# cpu2_lock_control2.net
KiCad netlist of a schematic drawn in Altium Designer
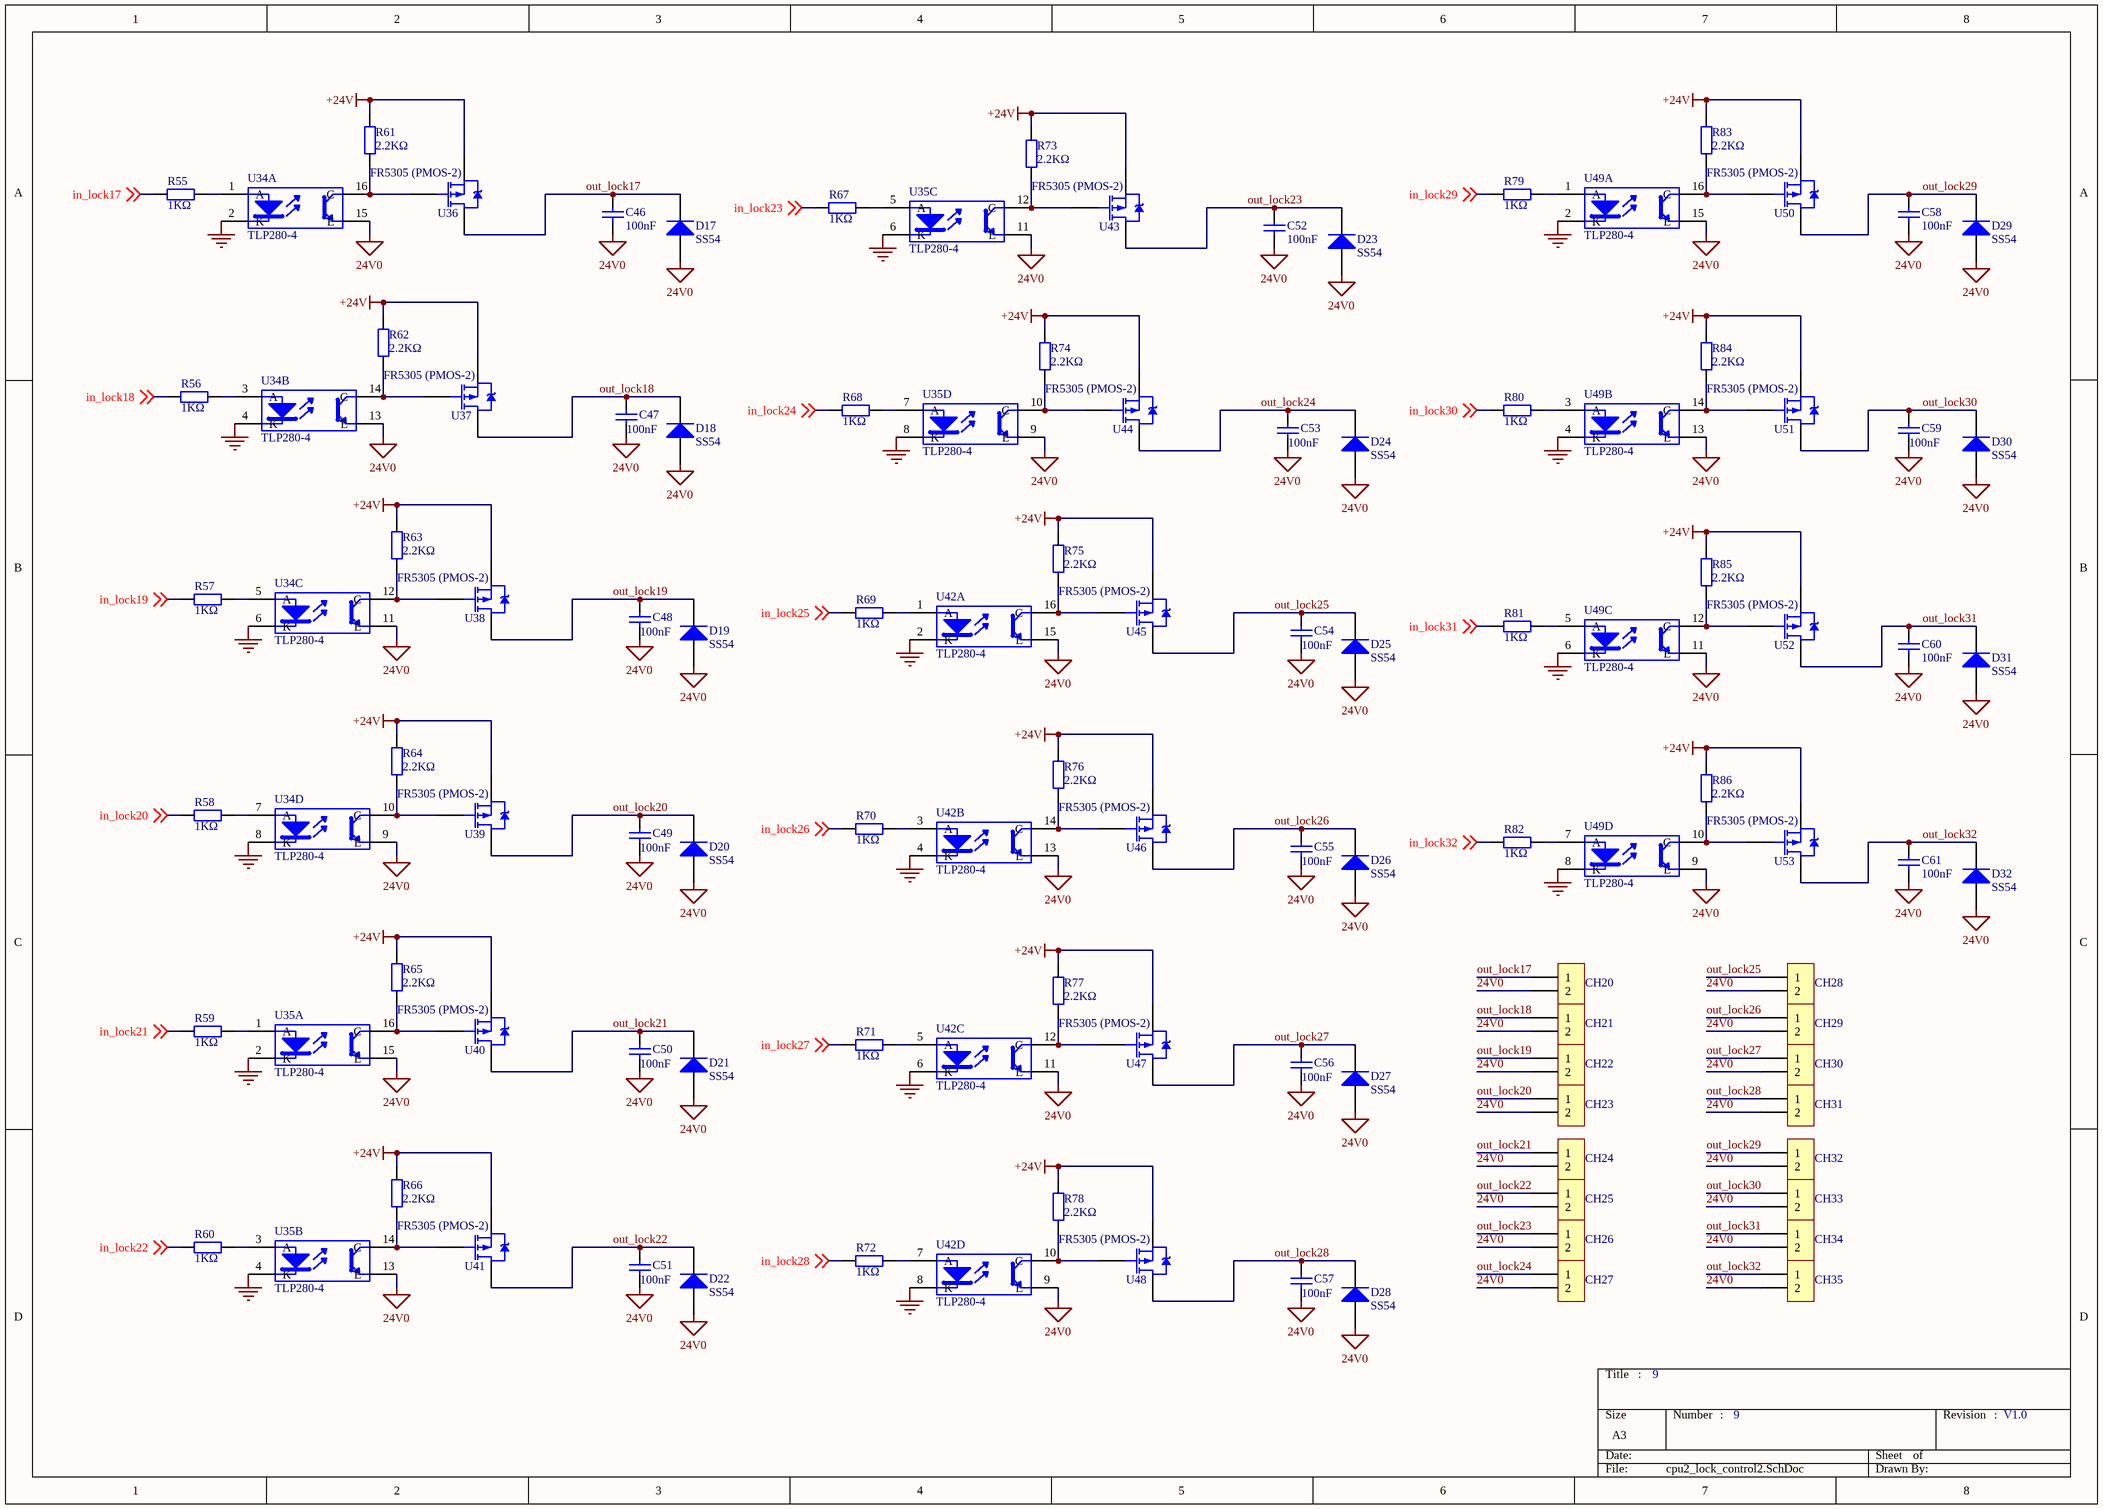
[diagram p0: cpu2_lock_control2.SchDoc]

(export (version "E")
  (design (tool "Eeschema 10.0.6"))
  (components
    (comp (ref "C46")
      (value "100nF")
      (footprint "0805_C")
      (description "贴片电容")
      (libsource (lib "Miscellaneous Devices LC") (part "0805 100nF(104) 10% 50V"))
    )
    (comp (ref "C47")
      (value "100nF")
      (footprint "0805_C")
      (description "贴片电容")
      (libsource (lib "Miscellaneous Devices LC") (part "0805 100nF(104) 10% 50V"))
    )
    (comp (ref "C48")
      (value "100nF")
      (footprint "0805_C")
      (description "贴片电容")
      (libsource (lib "Miscellaneous Devices LC") (part "0805 100nF(104) 10% 50V"))
    )
    (comp (ref "C49")
      (value "100nF")
      (footprint "0805_C")
      (description "贴片电容")
      (libsource (lib "Miscellaneous Devices LC") (part "0805 100nF(104) 10% 50V"))
    )
    (comp (ref "C50")
      (value "100nF")
      (footprint "0805_C")
      (description "贴片电容")
      (libsource (lib "Miscellaneous Devices LC") (part "0805 100nF(104) 10% 50V"))
    )
    (comp (ref "C51")
      (value "100nF")
      (footprint "0805_C")
      (description "贴片电容")
      (libsource (lib "Miscellaneous Devices LC") (part "0805 100nF(104) 10% 50V"))
    )
    (comp (ref "C52")
      (value "100nF")
      (footprint "0805_C")
      (description "贴片电容")
      (libsource (lib "Miscellaneous Devices LC") (part "0805 100nF(104) 10% 50V"))
    )
    (comp (ref "C53")
      (value "100nF")
      (footprint "0805_C")
      (description "贴片电容")
      (libsource (lib "Miscellaneous Devices LC") (part "0805 100nF(104) 10% 50V"))
    )
    (comp (ref "C54")
      (value "100nF")
      (footprint "0805_C")
      (description "贴片电容")
      (libsource (lib "Miscellaneous Devices LC") (part "0805 100nF(104) 10% 50V"))
    )
    (comp (ref "C55")
      (value "100nF")
      (footprint "0805_C")
      (description "贴片电容")
      (libsource (lib "Miscellaneous Devices LC") (part "0805 100nF(104) 10% 50V"))
    )
    (comp (ref "C56")
      (value "100nF")
      (footprint "0805_C")
      (description "贴片电容")
      (libsource (lib "Miscellaneous Devices LC") (part "0805 100nF(104) 10% 50V"))
    )
    (comp (ref "C57")
      (value "100nF")
      (footprint "0805_C")
      (description "贴片电容")
      (libsource (lib "Miscellaneous Devices LC") (part "0805 100nF(104) 10% 50V"))
    )
    (comp (ref "C58")
      (value "100nF")
      (footprint "0805_C")
      (description "贴片电容")
      (libsource (lib "Miscellaneous Devices LC") (part "0805 100nF(104) 10% 50V"))
    )
    (comp (ref "C59")
      (value "100nF")
      (footprint "0805_C")
      (description "贴片电容")
      (libsource (lib "Miscellaneous Devices LC") (part "0805 100nF(104) 10% 50V"))
    )
    (comp (ref "C60")
      (value "100nF")
      (footprint "0805_C")
      (description "贴片电容")
      (libsource (lib "Miscellaneous Devices LC") (part "0805 100nF(104) 10% 50V"))
    )
    (comp (ref "C61")
      (value "100nF")
      (footprint "0805_C")
      (description "贴片电容")
      (libsource (lib "Miscellaneous Devices LC") (part "0805 100nF(104) 10% 50V"))
    )
    (comp (ref "CH20")
      (value "HEADER1X2")
      (footprint "CH3.96-2PIN")
      (libsource (lib "myIntegrated_Library1") (part "HEADER1X2"))
    )
    (comp (ref "CH21")
      (value "HEADER1X2")
      (footprint "CH3.96-2PIN")
      (libsource (lib "myIntegrated_Library1") (part "HEADER1X2"))
    )
    (comp (ref "CH22")
      (value "HEADER1X2")
      (footprint "CH3.96-2PIN")
      (libsource (lib "myIntegrated_Library1") (part "HEADER1X2"))
    )
    (comp (ref "CH23")
      (value "HEADER1X2")
      (footprint "CH3.96-2PIN")
      (libsource (lib "myIntegrated_Library1") (part "HEADER1X2"))
    )
    (comp (ref "CH24")
      (value "HEADER1X2")
      (footprint "CH3.96-2PIN")
      (libsource (lib "myIntegrated_Library1") (part "HEADER1X2"))
    )
    (comp (ref "CH25")
      (value "HEADER1X2")
      (footprint "CH3.96-2PIN")
      (libsource (lib "myIntegrated_Library1") (part "HEADER1X2"))
    )
    (comp (ref "CH26")
      (value "HEADER1X2")
      (footprint "CH3.96-2PIN")
      (libsource (lib "myIntegrated_Library1") (part "HEADER1X2"))
    )
    (comp (ref "CH27")
      (value "HEADER1X2")
      (footprint "CH3.96-2PIN")
      (libsource (lib "myIntegrated_Library1") (part "HEADER1X2"))
    )
    (comp (ref "CH28")
      (value "HEADER1X2")
      (footprint "CH3.96-2PIN")
      (libsource (lib "myIntegrated_Library1") (part "HEADER1X2"))
    )
    (comp (ref "CH29")
      (value "HEADER1X2")
      (footprint "CH3.96-2PIN")
      (libsource (lib "myIntegrated_Library1") (part "HEADER1X2"))
    )
    (comp (ref "CH30")
      (value "HEADER1X2")
      (footprint "CH3.96-2PIN")
      (libsource (lib "myIntegrated_Library1") (part "HEADER1X2"))
    )
    (comp (ref "CH31")
      (value "HEADER1X2")
      (footprint "CH3.96-2PIN")
      (libsource (lib "myIntegrated_Library1") (part "HEADER1X2"))
    )
    (comp (ref "CH32")
      (value "HEADER1X2")
      (footprint "CH3.96-2PIN")
      (libsource (lib "myIntegrated_Library1") (part "HEADER1X2"))
    )
    (comp (ref "CH33")
      (value "HEADER1X2")
      (footprint "CH3.96-2PIN")
      (libsource (lib "myIntegrated_Library1") (part "HEADER1X2"))
    )
    (comp (ref "CH34")
      (value "HEADER1X2")
      (footprint "CH3.96-2PIN")
      (libsource (lib "myIntegrated_Library1") (part "HEADER1X2"))
    )
    (comp (ref "CH35")
      (value "HEADER1X2")
      (footprint "CH3.96-2PIN")
      (libsource (lib "myIntegrated_Library1") (part "HEADER1X2"))
    )
    (comp (ref "D17")
      (value "SS54")
      (footprint "SMA(DO-214AC)_S1")
      (description "二极管")
      (libsource (lib "Miscellaneous Devices LC") (part "SMA(DO-214AC) SS54"))
    )
    (comp (ref "D18")
      (value "SS54")
      (footprint "SMA(DO-214AC)_S1")
      (description "二极管")
      (libsource (lib "Miscellaneous Devices LC") (part "SMA(DO-214AC) SS54"))
    )
    (comp (ref "D19")
      (value "SS54")
      (footprint "SMA(DO-214AC)_S1")
      (description "二极管")
      (libsource (lib "Miscellaneous Devices LC") (part "SMA(DO-214AC) SS54"))
    )
    (comp (ref "D20")
      (value "SS54")
      (footprint "SMA(DO-214AC)_S1")
      (description "二极管")
      (libsource (lib "Miscellaneous Devices LC") (part "SMA(DO-214AC) SS54"))
    )
    (comp (ref "D21")
      (value "SS54")
      (footprint "SMA(DO-214AC)_S1")
      (description "二极管")
      (libsource (lib "Miscellaneous Devices LC") (part "SMA(DO-214AC) SS54"))
    )
    (comp (ref "D22")
      (value "SS54")
      (footprint "SMA(DO-214AC)_S1")
      (description "二极管")
      (libsource (lib "Miscellaneous Devices LC") (part "SMA(DO-214AC) SS54"))
    )
    (comp (ref "D23")
      (value "SS54")
      (footprint "SMA(DO-214AC)_S1")
      (description "二极管")
      (libsource (lib "Miscellaneous Devices LC") (part "SMA(DO-214AC) SS54"))
    )
    (comp (ref "D24")
      (value "SS54")
      (footprint "SMA(DO-214AC)_S1")
      (description "二极管")
      (libsource (lib "Miscellaneous Devices LC") (part "SMA(DO-214AC) SS54"))
    )
    (comp (ref "D25")
      (value "SS54")
      (footprint "SMA(DO-214AC)_S1")
      (description "二极管")
      (libsource (lib "Miscellaneous Devices LC") (part "SMA(DO-214AC) SS54"))
    )
    (comp (ref "D26")
      (value "SS54")
      (footprint "SMA(DO-214AC)_S1")
      (description "二极管")
      (libsource (lib "Miscellaneous Devices LC") (part "SMA(DO-214AC) SS54"))
    )
    (comp (ref "D27")
      (value "SS54")
      (footprint "SMA(DO-214AC)_S1")
      (description "二极管")
      (libsource (lib "Miscellaneous Devices LC") (part "SMA(DO-214AC) SS54"))
    )
    (comp (ref "D28")
      (value "SS54")
      (footprint "SMA(DO-214AC)_S1")
      (description "二极管")
      (libsource (lib "Miscellaneous Devices LC") (part "SMA(DO-214AC) SS54"))
    )
    (comp (ref "D29")
      (value "SS54")
      (footprint "SMA(DO-214AC)_S1")
      (description "二极管")
      (libsource (lib "Miscellaneous Devices LC") (part "SMA(DO-214AC) SS54"))
    )
    (comp (ref "D30")
      (value "SS54")
      (footprint "SMA(DO-214AC)_S1")
      (description "二极管")
      (libsource (lib "Miscellaneous Devices LC") (part "SMA(DO-214AC) SS54"))
    )
    (comp (ref "D31")
      (value "SS54")
      (footprint "SMA(DO-214AC)_S1")
      (description "二极管")
      (libsource (lib "Miscellaneous Devices LC") (part "SMA(DO-214AC) SS54"))
    )
    (comp (ref "D32")
      (value "SS54")
      (footprint "SMA(DO-214AC)_S1")
      (description "二极管")
      (libsource (lib "Miscellaneous Devices LC") (part "SMA(DO-214AC) SS54"))
    )
    (comp (ref "R55")
      (value "1KΩ")
      (footprint "0805_R")
      (description "贴片电阻")
      (libsource (lib "") (part "0805 11KΩ (1102) 1%_1"))
    )
    (comp (ref "R56")
      (value "1KΩ")
      (footprint "0805_R")
      (description "贴片电阻")
      (libsource (lib "") (part "0805 11KΩ (1102) 1%_1"))
    )
    (comp (ref "R57")
      (value "1KΩ")
      (footprint "0805_R")
      (description "贴片电阻")
      (libsource (lib "") (part "0805 11KΩ (1102) 1%_1"))
    )
    (comp (ref "R58")
      (value "1KΩ")
      (footprint "0805_R")
      (description "贴片电阻")
      (libsource (lib "") (part "0805 11KΩ (1102) 1%_1"))
    )
    (comp (ref "R59")
      (value "1KΩ")
      (footprint "0805_R")
      (description "贴片电阻")
      (libsource (lib "") (part "0805 11KΩ (1102) 1%_1"))
    )
    (comp (ref "R60")
      (value "1KΩ")
      (footprint "0805_R")
      (description "贴片电阻")
      (libsource (lib "") (part "0805 11KΩ (1102) 1%_1"))
    )
    (comp (ref "R61")
      (value "2.2KΩ")
      (footprint "0805_R")
      (description "贴片电阻")
      (libsource (lib "Miscellaneous Devices LC") (part "0805 11KΩ (1102) 1%"))
    )
    (comp (ref "R62")
      (value "2.2KΩ")
      (footprint "0805_R")
      (description "贴片电阻")
      (libsource (lib "Miscellaneous Devices LC") (part "0805 11KΩ (1102) 1%"))
    )
    (comp (ref "R63")
      (value "2.2KΩ")
      (footprint "0805_R")
      (description "贴片电阻")
      (libsource (lib "Miscellaneous Devices LC") (part "0805 11KΩ (1102) 1%"))
    )
    (comp (ref "R64")
      (value "2.2KΩ")
      (footprint "0805_R")
      (description "贴片电阻")
      (libsource (lib "Miscellaneous Devices LC") (part "0805 11KΩ (1102) 1%"))
    )
    (comp (ref "R65")
      (value "2.2KΩ")
      (footprint "0805_R")
      (description "贴片电阻")
      (libsource (lib "Miscellaneous Devices LC") (part "0805 11KΩ (1102) 1%"))
    )
    (comp (ref "R66")
      (value "2.2KΩ")
      (footprint "0805_R")
      (description "贴片电阻")
      (libsource (lib "Miscellaneous Devices LC") (part "0805 11KΩ (1102) 1%"))
    )
    (comp (ref "R67")
      (value "1KΩ")
      (footprint "0805_R")
      (description "贴片电阻")
      (libsource (lib "") (part "0805 11KΩ (1102) 1%_1"))
    )
    (comp (ref "R68")
      (value "1KΩ")
      (footprint "0805_R")
      (description "贴片电阻")
      (libsource (lib "") (part "0805 11KΩ (1102) 1%_1"))
    )
    (comp (ref "R69")
      (value "1KΩ")
      (footprint "0805_R")
      (description "贴片电阻")
      (libsource (lib "") (part "0805 11KΩ (1102) 1%_1"))
    )
    (comp (ref "R70")
      (value "1KΩ")
      (footprint "0805_R")
      (description "贴片电阻")
      (libsource (lib "") (part "0805 11KΩ (1102) 1%_1"))
    )
    (comp (ref "R71")
      (value "1KΩ")
      (footprint "0805_R")
      (description "贴片电阻")
      (libsource (lib "") (part "0805 11KΩ (1102) 1%_1"))
    )
    (comp (ref "R72")
      (value "1KΩ")
      (footprint "0805_R")
      (description "贴片电阻")
      (libsource (lib "") (part "0805 11KΩ (1102) 1%_1"))
    )
    (comp (ref "R73")
      (value "2.2KΩ")
      (footprint "0805_R")
      (description "贴片电阻")
      (libsource (lib "Miscellaneous Devices LC") (part "0805 11KΩ (1102) 1%"))
    )
    (comp (ref "R74")
      (value "2.2KΩ")
      (footprint "0805_R")
      (description "贴片电阻")
      (libsource (lib "Miscellaneous Devices LC") (part "0805 11KΩ (1102) 1%"))
    )
    (comp (ref "R75")
      (value "2.2KΩ")
      (footprint "0805_R")
      (description "贴片电阻")
      (libsource (lib "Miscellaneous Devices LC") (part "0805 11KΩ (1102) 1%"))
    )
    (comp (ref "R76")
      (value "2.2KΩ")
      (footprint "0805_R")
      (description "贴片电阻")
      (libsource (lib "Miscellaneous Devices LC") (part "0805 11KΩ (1102) 1%"))
    )
    (comp (ref "R77")
      (value "2.2KΩ")
      (footprint "0805_R")
      (description "贴片电阻")
      (libsource (lib "Miscellaneous Devices LC") (part "0805 11KΩ (1102) 1%"))
    )
    (comp (ref "R78")
      (value "2.2KΩ")
      (footprint "0805_R")
      (description "贴片电阻")
      (libsource (lib "Miscellaneous Devices LC") (part "0805 11KΩ (1102) 1%"))
    )
    (comp (ref "R79")
      (value "1KΩ")
      (footprint "0805_R")
      (description "贴片电阻")
      (libsource (lib "") (part "0805 11KΩ (1102) 1%_1"))
    )
    (comp (ref "R80")
      (value "1KΩ")
      (footprint "0805_R")
      (description "贴片电阻")
      (libsource (lib "") (part "0805 11KΩ (1102) 1%_1"))
    )
    (comp (ref "R81")
      (value "1KΩ")
      (footprint "0805_R")
      (description "贴片电阻")
      (libsource (lib "") (part "0805 11KΩ (1102) 1%_1"))
    )
    (comp (ref "R82")
      (value "1KΩ")
      (footprint "0805_R")
      (description "贴片电阻")
      (libsource (lib "") (part "0805 11KΩ (1102) 1%_1"))
    )
    (comp (ref "R83")
      (value "2.2KΩ")
      (footprint "0805_R")
      (description "贴片电阻")
      (libsource (lib "Miscellaneous Devices LC") (part "0805 11KΩ (1102) 1%"))
    )
    (comp (ref "R84")
      (value "2.2KΩ")
      (footprint "0805_R")
      (description "贴片电阻")
      (libsource (lib "Miscellaneous Devices LC") (part "0805 11KΩ (1102) 1%"))
    )
    (comp (ref "R85")
      (value "2.2KΩ")
      (footprint "0805_R")
      (description "贴片电阻")
      (libsource (lib "Miscellaneous Devices LC") (part "0805 11KΩ (1102) 1%"))
    )
    (comp (ref "R86")
      (value "2.2KΩ")
      (footprint "0805_R")
      (description "贴片电阻")
      (libsource (lib "Miscellaneous Devices LC") (part "0805 11KΩ (1102) 1%"))
    )
    (comp (ref "U34") (value "TLP280-4") (footprint "SO16") (libsource (lib "WH V20") (part "TLP521-4")))
    (comp (ref "U35") (value "TLP280-4") (footprint "SO16") (libsource (lib "WH V20") (part "TLP521-4")))
    (comp (ref "U36")
      (value "FR5305 (PMOS-2)")
      (footprint "TO-252")
      (description "P-Channel Power MOSFET")
      (fields (field (name "PUBLISHER") "Altium Limited"))
      (libsource (lib "Miscellaneous Devices") (part "PMOS-2"))
    )
    (comp (ref "U37")
      (value "FR5305 (PMOS-2)")
      (footprint "TO-252")
      (description "P-Channel Power MOSFET")
      (fields (field (name "PUBLISHER") "Altium Limited"))
      (libsource (lib "Miscellaneous Devices") (part "PMOS-2"))
    )
    (comp (ref "U38")
      (value "FR5305 (PMOS-2)")
      (footprint "TO-252")
      (description "P-Channel Power MOSFET")
      (fields (field (name "PUBLISHER") "Altium Limited"))
      (libsource (lib "Miscellaneous Devices") (part "PMOS-2"))
    )
    (comp (ref "U39")
      (value "FR5305 (PMOS-2)")
      (footprint "TO-252")
      (description "P-Channel Power MOSFET")
      (fields (field (name "PUBLISHER") "Altium Limited"))
      (libsource (lib "Miscellaneous Devices") (part "PMOS-2"))
    )
    (comp (ref "U40")
      (value "FR5305 (PMOS-2)")
      (footprint "TO-252")
      (description "P-Channel Power MOSFET")
      (fields (field (name "PUBLISHER") "Altium Limited"))
      (libsource (lib "Miscellaneous Devices") (part "PMOS-2"))
    )
    (comp (ref "U41")
      (value "FR5305 (PMOS-2)")
      (footprint "TO-252")
      (description "P-Channel Power MOSFET")
      (fields (field (name "PUBLISHER") "Altium Limited"))
      (libsource (lib "Miscellaneous Devices") (part "PMOS-2"))
    )
    (comp (ref "U42") (value "TLP280-4") (footprint "SO16") (libsource (lib "WH V20") (part "TLP521-4")))
    (comp (ref "U43")
      (value "FR5305 (PMOS-2)")
      (footprint "TO-252")
      (description "P-Channel Power MOSFET")
      (fields (field (name "PUBLISHER") "Altium Limited"))
      (libsource (lib "Miscellaneous Devices") (part "PMOS-2"))
    )
    (comp (ref "U44")
      (value "FR5305 (PMOS-2)")
      (footprint "TO-252")
      (description "P-Channel Power MOSFET")
      (fields (field (name "PUBLISHER") "Altium Limited"))
      (libsource (lib "Miscellaneous Devices") (part "PMOS-2"))
    )
    (comp (ref "U45")
      (value "FR5305 (PMOS-2)")
      (footprint "TO-252")
      (description "P-Channel Power MOSFET")
      (fields (field (name "PUBLISHER") "Altium Limited"))
      (libsource (lib "Miscellaneous Devices") (part "PMOS-2"))
    )
    (comp (ref "U46")
      (value "FR5305 (PMOS-2)")
      (footprint "TO-252")
      (description "P-Channel Power MOSFET")
      (fields (field (name "PUBLISHER") "Altium Limited"))
      (libsource (lib "Miscellaneous Devices") (part "PMOS-2"))
    )
    (comp (ref "U47")
      (value "FR5305 (PMOS-2)")
      (footprint "TO-252")
      (description "P-Channel Power MOSFET")
      (fields (field (name "PUBLISHER") "Altium Limited"))
      (libsource (lib "Miscellaneous Devices") (part "PMOS-2"))
    )
    (comp (ref "U48")
      (value "FR5305 (PMOS-2)")
      (footprint "TO-252")
      (description "P-Channel Power MOSFET")
      (fields (field (name "PUBLISHER") "Altium Limited"))
      (libsource (lib "Miscellaneous Devices") (part "PMOS-2"))
    )
    (comp (ref "U49") (value "TLP280-4") (footprint "SO16") (libsource (lib "WH V20") (part "TLP521-4")))
    (comp (ref "U50")
      (value "FR5305 (PMOS-2)")
      (footprint "TO-252")
      (description "P-Channel Power MOSFET")
      (fields (field (name "PUBLISHER") "Altium Limited"))
      (libsource (lib "Miscellaneous Devices") (part "PMOS-2"))
    )
    (comp (ref "U51")
      (value "FR5305 (PMOS-2)")
      (footprint "TO-252")
      (description "P-Channel Power MOSFET")
      (fields (field (name "PUBLISHER") "Altium Limited"))
      (libsource (lib "Miscellaneous Devices") (part "PMOS-2"))
    )
    (comp (ref "U52")
      (value "FR5305 (PMOS-2)")
      (footprint "TO-252")
      (description "P-Channel Power MOSFET")
      (fields (field (name "PUBLISHER") "Altium Limited"))
      (libsource (lib "Miscellaneous Devices") (part "PMOS-2"))
    )
    (comp (ref "U53")
      (value "FR5305 (PMOS-2)")
      (footprint "TO-252")
      (description "P-Channel Power MOSFET")
      (fields (field (name "PUBLISHER") "Altium Limited"))
      (libsource (lib "Miscellaneous Devices") (part "PMOS-2"))
    )
  )
  (nets
    (net (code "1") (name "+24V") (class "Default")
      (node (ref "R61") (pin "2") (pinfunction "2_2") (pintype "passive"))
      (node (ref "R62") (pin "2") (pinfunction "2_2") (pintype "passive"))
      (node (ref "R63") (pin "2") (pinfunction "2_2") (pintype "passive"))
      (node (ref "R64") (pin "2") (pinfunction "2_2") (pintype "passive"))
      (node (ref "R65") (pin "2") (pinfunction "2_2") (pintype "passive"))
      (node (ref "R66") (pin "2") (pinfunction "2_2") (pintype "passive"))
      (node (ref "R73") (pin "2") (pinfunction "2_2") (pintype "passive"))
      (node (ref "R74") (pin "2") (pinfunction "2_2") (pintype "passive"))
      (node (ref "R75") (pin "2") (pinfunction "2_2") (pintype "passive"))
      (node (ref "R76") (pin "2") (pinfunction "2_2") (pintype "passive"))
      (node (ref "R77") (pin "2") (pinfunction "2_2") (pintype "passive"))
      (node (ref "R78") (pin "2") (pinfunction "2_2") (pintype "passive"))
      (node (ref "R83") (pin "2") (pinfunction "2_2") (pintype "passive"))
      (node (ref "R84") (pin "2") (pinfunction "2_2") (pintype "passive"))
      (node (ref "R85") (pin "2") (pinfunction "2_2") (pintype "passive"))
      (node (ref "R86") (pin "2") (pinfunction "2_2") (pintype "passive"))
      (node (ref "U36") (pin "3") (pinfunction "S_3") (pintype "passive"))
      (node (ref "U37") (pin "3") (pinfunction "S_3") (pintype "passive"))
      (node (ref "U38") (pin "3") (pinfunction "S_3") (pintype "passive"))
      (node (ref "U39") (pin "3") (pinfunction "S_3") (pintype "passive"))
      (node (ref "U40") (pin "3") (pinfunction "S_3") (pintype "passive"))
      (node (ref "U41") (pin "3") (pinfunction "S_3") (pintype "passive"))
      (node (ref "U43") (pin "3") (pinfunction "S_3") (pintype "passive"))
      (node (ref "U44") (pin "3") (pinfunction "S_3") (pintype "passive"))
      (node (ref "U45") (pin "3") (pinfunction "S_3") (pintype "passive"))
      (node (ref "U46") (pin "3") (pinfunction "S_3") (pintype "passive"))
      (node (ref "U47") (pin "3") (pinfunction "S_3") (pintype "passive"))
      (node (ref "U48") (pin "3") (pinfunction "S_3") (pintype "passive"))
      (node (ref "U50") (pin "3") (pinfunction "S_3") (pintype "passive"))
      (node (ref "U51") (pin "3") (pinfunction "S_3") (pintype "passive"))
      (node (ref "U52") (pin "3") (pinfunction "S_3") (pintype "passive"))
      (node (ref "U53") (pin "3") (pinfunction "S_3") (pintype "passive"))
    )
    (net (code "2") (name "/out_lock17") (class "Default")
      (node (ref "C46") (pin "2") (pinfunction "2_2") (pintype "passive"))
      (node (ref "CH20") (pin "1") (pinfunction "1_1") (pintype "passive"))
      (node (ref "D17") (pin "2") (pinfunction "K_2") (pintype "passive"))
      (node (ref "U36") (pin "2") (pinfunction "D_2") (pintype "passive"))
    )
    (net (code "3") (name "/out_lock18") (class "Default")
      (node (ref "C47") (pin "2") (pinfunction "2_2") (pintype "passive"))
      (node (ref "CH21") (pin "1") (pinfunction "1_1") (pintype "passive"))
      (node (ref "D18") (pin "2") (pinfunction "K_2") (pintype "passive"))
      (node (ref "U37") (pin "2") (pinfunction "D_2") (pintype "passive"))
    )
    (net (code "4") (name "/out_lock19") (class "Default")
      (node (ref "C48") (pin "2") (pinfunction "2_2") (pintype "passive"))
      (node (ref "CH22") (pin "1") (pinfunction "1_1") (pintype "passive"))
      (node (ref "D19") (pin "2") (pinfunction "K_2") (pintype "passive"))
      (node (ref "U38") (pin "2") (pinfunction "D_2") (pintype "passive"))
    )
    (net (code "5") (name "/out_lock20") (class "Default")
      (node (ref "C49") (pin "2") (pinfunction "2_2") (pintype "passive"))
      (node (ref "CH23") (pin "1") (pinfunction "1_1") (pintype "passive"))
      (node (ref "D20") (pin "2") (pinfunction "K_2") (pintype "passive"))
      (node (ref "U39") (pin "2") (pinfunction "D_2") (pintype "passive"))
    )
    (net (code "6") (name "/out_lock21") (class "Default")
      (node (ref "C50") (pin "2") (pinfunction "2_2") (pintype "passive"))
      (node (ref "CH24") (pin "1") (pinfunction "1_1") (pintype "passive"))
      (node (ref "D21") (pin "2") (pinfunction "K_2") (pintype "passive"))
      (node (ref "U40") (pin "2") (pinfunction "D_2") (pintype "passive"))
    )
    (net (code "7") (name "/out_lock22") (class "Default")
      (node (ref "C51") (pin "2") (pinfunction "2_2") (pintype "passive"))
      (node (ref "CH25") (pin "1") (pinfunction "1_1") (pintype "passive"))
      (node (ref "D22") (pin "2") (pinfunction "K_2") (pintype "passive"))
      (node (ref "U41") (pin "2") (pinfunction "D_2") (pintype "passive"))
    )
    (net (code "8") (name "/out_lock23") (class "Default")
      (node (ref "C52") (pin "2") (pinfunction "2_2") (pintype "passive"))
      (node (ref "CH26") (pin "1") (pinfunction "1_1") (pintype "passive"))
      (node (ref "D23") (pin "2") (pinfunction "K_2") (pintype "passive"))
      (node (ref "U43") (pin "2") (pinfunction "D_2") (pintype "passive"))
    )
    (net (code "9") (name "/out_lock24") (class "Default")
      (node (ref "C53") (pin "2") (pinfunction "2_2") (pintype "passive"))
      (node (ref "CH27") (pin "1") (pinfunction "1_1") (pintype "passive"))
      (node (ref "D24") (pin "2") (pinfunction "K_2") (pintype "passive"))
      (node (ref "U44") (pin "2") (pinfunction "D_2") (pintype "passive"))
    )
    (net (code "10") (name "/out_lock25") (class "Default")
      (node (ref "C54") (pin "2") (pinfunction "2_2") (pintype "passive"))
      (node (ref "CH28") (pin "1") (pinfunction "1_1") (pintype "passive"))
      (node (ref "D25") (pin "2") (pinfunction "K_2") (pintype "passive"))
      (node (ref "U45") (pin "2") (pinfunction "D_2") (pintype "passive"))
    )
    (net (code "11") (name "/out_lock26") (class "Default")
      (node (ref "C55") (pin "2") (pinfunction "2_2") (pintype "passive"))
      (node (ref "CH29") (pin "1") (pinfunction "1_1") (pintype "passive"))
      (node (ref "D26") (pin "2") (pinfunction "K_2") (pintype "passive"))
      (node (ref "U46") (pin "2") (pinfunction "D_2") (pintype "passive"))
    )
    (net (code "12") (name "/out_lock27") (class "Default")
      (node (ref "C56") (pin "2") (pinfunction "2_2") (pintype "passive"))
      (node (ref "CH30") (pin "1") (pinfunction "1_1") (pintype "passive"))
      (node (ref "D27") (pin "2") (pinfunction "K_2") (pintype "passive"))
      (node (ref "U47") (pin "2") (pinfunction "D_2") (pintype "passive"))
    )
    (net (code "13") (name "/out_lock28") (class "Default")
      (node (ref "C57") (pin "2") (pinfunction "2_2") (pintype "passive"))
      (node (ref "CH31") (pin "1") (pinfunction "1_1") (pintype "passive"))
      (node (ref "D28") (pin "2") (pinfunction "K_2") (pintype "passive"))
      (node (ref "U48") (pin "2") (pinfunction "D_2") (pintype "passive"))
    )
    (net (code "14") (name "/out_lock29") (class "Default")
      (node (ref "C58") (pin "2") (pinfunction "2_2") (pintype "passive"))
      (node (ref "CH32") (pin "1") (pinfunction "1_1") (pintype "passive"))
      (node (ref "D29") (pin "2") (pinfunction "K_2") (pintype "passive"))
      (node (ref "U50") (pin "2") (pinfunction "D_2") (pintype "passive"))
    )
    (net (code "15") (name "/out_lock30") (class "Default")
      (node (ref "C59") (pin "2") (pinfunction "2_2") (pintype "passive"))
      (node (ref "CH33") (pin "1") (pinfunction "1_1") (pintype "passive"))
      (node (ref "D30") (pin "2") (pinfunction "K_2") (pintype "passive"))
      (node (ref "U51") (pin "2") (pinfunction "D_2") (pintype "passive"))
    )
    (net (code "16") (name "/out_lock31") (class "Default")
      (node (ref "C60") (pin "2") (pinfunction "2_2") (pintype "passive"))
      (node (ref "CH34") (pin "1") (pinfunction "1_1") (pintype "passive"))
      (node (ref "D31") (pin "2") (pinfunction "K_2") (pintype "passive"))
      (node (ref "U52") (pin "2") (pinfunction "D_2") (pintype "passive"))
    )
    (net (code "17") (name "/out_lock32") (class "Default")
      (node (ref "C61") (pin "2") (pinfunction "2_2") (pintype "passive"))
      (node (ref "CH35") (pin "1") (pinfunction "1_1") (pintype "passive"))
      (node (ref "D32") (pin "2") (pinfunction "K_2") (pintype "passive"))
      (node (ref "U53") (pin "2") (pinfunction "D_2") (pintype "passive"))
    )
    (net (code "18") (name "24V0") (class "Default")
      (node (ref "C46") (pin "1") (pinfunction "1_1") (pintype "passive"))
      (node (ref "C47") (pin "1") (pinfunction "1_1") (pintype "passive"))
      (node (ref "C48") (pin "1") (pinfunction "1_1") (pintype "passive"))
      (node (ref "C49") (pin "1") (pinfunction "1_1") (pintype "passive"))
      (node (ref "C50") (pin "1") (pinfunction "1_1") (pintype "passive"))
      (node (ref "C51") (pin "1") (pinfunction "1_1") (pintype "passive"))
      (node (ref "C52") (pin "1") (pinfunction "1_1") (pintype "passive"))
      (node (ref "C53") (pin "1") (pinfunction "1_1") (pintype "passive"))
      (node (ref "C54") (pin "1") (pinfunction "1_1") (pintype "passive"))
      (node (ref "C55") (pin "1") (pinfunction "1_1") (pintype "passive"))
      (node (ref "C56") (pin "1") (pinfunction "1_1") (pintype "passive"))
      (node (ref "C57") (pin "1") (pinfunction "1_1") (pintype "passive"))
      (node (ref "C58") (pin "1") (pinfunction "1_1") (pintype "passive"))
      (node (ref "C59") (pin "1") (pinfunction "1_1") (pintype "passive"))
      (node (ref "C60") (pin "1") (pinfunction "1_1") (pintype "passive"))
      (node (ref "C61") (pin "1") (pinfunction "1_1") (pintype "passive"))
      (node (ref "CH20") (pin "2") (pinfunction "2_2") (pintype "passive"))
      (node (ref "CH21") (pin "2") (pinfunction "2_2") (pintype "passive"))
      (node (ref "CH22") (pin "2") (pinfunction "2_2") (pintype "passive"))
      (node (ref "CH23") (pin "2") (pinfunction "2_2") (pintype "passive"))
      (node (ref "CH24") (pin "2") (pinfunction "2_2") (pintype "passive"))
      (node (ref "CH25") (pin "2") (pinfunction "2_2") (pintype "passive"))
      (node (ref "CH26") (pin "2") (pinfunction "2_2") (pintype "passive"))
      (node (ref "CH27") (pin "2") (pinfunction "2_2") (pintype "passive"))
      (node (ref "CH28") (pin "2") (pinfunction "2_2") (pintype "passive"))
      (node (ref "CH29") (pin "2") (pinfunction "2_2") (pintype "passive"))
      (node (ref "CH30") (pin "2") (pinfunction "2_2") (pintype "passive"))
      (node (ref "CH31") (pin "2") (pinfunction "2_2") (pintype "passive"))
      (node (ref "CH32") (pin "2") (pinfunction "2_2") (pintype "passive"))
      (node (ref "CH33") (pin "2") (pinfunction "2_2") (pintype "passive"))
      (node (ref "CH34") (pin "2") (pinfunction "2_2") (pintype "passive"))
      (node (ref "CH35") (pin "2") (pinfunction "2_2") (pintype "passive"))
      (node (ref "D17") (pin "1") (pinfunction "A_1") (pintype "passive"))
      (node (ref "D18") (pin "1") (pinfunction "A_1") (pintype "passive"))
      (node (ref "D19") (pin "1") (pinfunction "A_1") (pintype "passive"))
      (node (ref "D20") (pin "1") (pinfunction "A_1") (pintype "passive"))
      (node (ref "D21") (pin "1") (pinfunction "A_1") (pintype "passive"))
      (node (ref "D22") (pin "1") (pinfunction "A_1") (pintype "passive"))
      (node (ref "D23") (pin "1") (pinfunction "A_1") (pintype "passive"))
      (node (ref "D24") (pin "1") (pinfunction "A_1") (pintype "passive"))
      (node (ref "D25") (pin "1") (pinfunction "A_1") (pintype "passive"))
      (node (ref "D26") (pin "1") (pinfunction "A_1") (pintype "passive"))
      (node (ref "D27") (pin "1") (pinfunction "A_1") (pintype "passive"))
      (node (ref "D28") (pin "1") (pinfunction "A_1") (pintype "passive"))
      (node (ref "D29") (pin "1") (pinfunction "A_1") (pintype "passive"))
      (node (ref "D30") (pin "1") (pinfunction "A_1") (pintype "passive"))
      (node (ref "D31") (pin "1") (pinfunction "A_1") (pintype "passive"))
      (node (ref "D32") (pin "1") (pinfunction "A_1") (pintype "passive"))
      (node (ref "U34") (pin "11") (pinfunction "E_11") (pintype "passive"))
      (node (ref "U34") (pin "13") (pinfunction "E_13") (pintype "passive"))
      (node (ref "U34") (pin "15") (pinfunction "E_15") (pintype "passive"))
      (node (ref "U34") (pin "9") (pinfunction "E_9") (pintype "passive"))
      (node (ref "U35") (pin "11") (pinfunction "E_11") (pintype "passive"))
      (node (ref "U35") (pin "13") (pinfunction "E_13") (pintype "passive"))
      (node (ref "U35") (pin "15") (pinfunction "E_15") (pintype "passive"))
      (node (ref "U35") (pin "9") (pinfunction "E_9") (pintype "passive"))
      (node (ref "U42") (pin "11") (pinfunction "E_11") (pintype "passive"))
      (node (ref "U42") (pin "13") (pinfunction "E_13") (pintype "passive"))
      (node (ref "U42") (pin "15") (pinfunction "E_15") (pintype "passive"))
      (node (ref "U42") (pin "9") (pinfunction "E_9") (pintype "passive"))
      (node (ref "U49") (pin "11") (pinfunction "E_11") (pintype "passive"))
      (node (ref "U49") (pin "13") (pinfunction "E_13") (pintype "passive"))
      (node (ref "U49") (pin "15") (pinfunction "E_15") (pintype "passive"))
      (node (ref "U49") (pin "9") (pinfunction "E_9") (pintype "passive"))
    )
    (net (code "19") (name "GND") (class "Default")
      (node (ref "U34") (pin "2") (pinfunction "K_2") (pintype "passive"))
      (node (ref "U34") (pin "4") (pinfunction "K_4") (pintype "passive"))
      (node (ref "U34") (pin "6") (pinfunction "K_6") (pintype "passive"))
      (node (ref "U34") (pin "8") (pinfunction "K_8") (pintype "passive"))
      (node (ref "U35") (pin "2") (pinfunction "K_2") (pintype "passive"))
      (node (ref "U35") (pin "4") (pinfunction "K_4") (pintype "passive"))
      (node (ref "U35") (pin "6") (pinfunction "K_6") (pintype "passive"))
      (node (ref "U35") (pin "8") (pinfunction "K_8") (pintype "passive"))
      (node (ref "U42") (pin "2") (pinfunction "K_2") (pintype "passive"))
      (node (ref "U42") (pin "4") (pinfunction "K_4") (pintype "passive"))
      (node (ref "U42") (pin "6") (pinfunction "K_6") (pintype "passive"))
      (node (ref "U42") (pin "8") (pinfunction "K_8") (pintype "passive"))
      (node (ref "U49") (pin "2") (pinfunction "K_2") (pintype "passive"))
      (node (ref "U49") (pin "4") (pinfunction "K_4") (pintype "passive"))
      (node (ref "U49") (pin "6") (pinfunction "K_6") (pintype "passive"))
      (node (ref "U49") (pin "8") (pinfunction "K_8") (pintype "passive"))
    )
    (net (code "20") (name "Net-(U34A-A)") (class "Default")
      (node (ref "R55") (pin "2") (pinfunction "2_2") (pintype "passive"))
      (node (ref "U34") (pin "1") (pinfunction "A_1") (pintype "passive"))
    )
    (net (code "21") (name "Net-(U34A-C)") (class "Default")
      (node (ref "R61") (pin "1") (pinfunction "1_1") (pintype "passive"))
      (node (ref "U34") (pin "16") (pinfunction "C_16") (pintype "passive"))
      (node (ref "U36") (pin "1") (pinfunction "G_1") (pintype "passive"))
    )
    (net (code "22") (name "Net-(U34B-A)") (class "Default")
      (node (ref "R56") (pin "2") (pinfunction "2_2") (pintype "passive"))
      (node (ref "U34") (pin "3") (pinfunction "A_3") (pintype "passive"))
    )
    (net (code "23") (name "Net-(U34B-C)") (class "Default")
      (node (ref "R62") (pin "1") (pinfunction "1_1") (pintype "passive"))
      (node (ref "U34") (pin "14") (pinfunction "C_14") (pintype "passive"))
      (node (ref "U37") (pin "1") (pinfunction "G_1") (pintype "passive"))
    )
    (net (code "24") (name "Net-(U34C-A)") (class "Default")
      (node (ref "R57") (pin "2") (pinfunction "2_2") (pintype "passive"))
      (node (ref "U34") (pin "5") (pinfunction "A_5") (pintype "passive"))
    )
    (net (code "25") (name "Net-(U34C-C)") (class "Default")
      (node (ref "R63") (pin "1") (pinfunction "1_1") (pintype "passive"))
      (node (ref "U34") (pin "12") (pinfunction "C_12") (pintype "passive"))
      (node (ref "U38") (pin "1") (pinfunction "G_1") (pintype "passive"))
    )
    (net (code "26") (name "Net-(U34D-A)") (class "Default")
      (node (ref "R58") (pin "2") (pinfunction "2_2") (pintype "passive"))
      (node (ref "U34") (pin "7") (pinfunction "A_7") (pintype "passive"))
    )
    (net (code "27") (name "Net-(U34D-C)") (class "Default")
      (node (ref "R64") (pin "1") (pinfunction "1_1") (pintype "passive"))
      (node (ref "U34") (pin "10") (pinfunction "C_10") (pintype "passive"))
      (node (ref "U39") (pin "1") (pinfunction "G_1") (pintype "passive"))
    )
    (net (code "28") (name "Net-(U35A-A)") (class "Default")
      (node (ref "R59") (pin "2") (pinfunction "2_2") (pintype "passive"))
      (node (ref "U35") (pin "1") (pinfunction "A_1") (pintype "passive"))
    )
    (net (code "29") (name "Net-(U35A-C)") (class "Default")
      (node (ref "R65") (pin "1") (pinfunction "1_1") (pintype "passive"))
      (node (ref "U35") (pin "16") (pinfunction "C_16") (pintype "passive"))
      (node (ref "U40") (pin "1") (pinfunction "G_1") (pintype "passive"))
    )
    (net (code "30") (name "Net-(U35B-A)") (class "Default")
      (node (ref "R60") (pin "2") (pinfunction "2_2") (pintype "passive"))
      (node (ref "U35") (pin "3") (pinfunction "A_3") (pintype "passive"))
    )
    (net (code "31") (name "Net-(U35B-C)") (class "Default")
      (node (ref "R66") (pin "1") (pinfunction "1_1") (pintype "passive"))
      (node (ref "U35") (pin "14") (pinfunction "C_14") (pintype "passive"))
      (node (ref "U41") (pin "1") (pinfunction "G_1") (pintype "passive"))
    )
    (net (code "32") (name "Net-(U35C-A)") (class "Default")
      (node (ref "R67") (pin "2") (pinfunction "2_2") (pintype "passive"))
      (node (ref "U35") (pin "5") (pinfunction "A_5") (pintype "passive"))
    )
    (net (code "33") (name "Net-(U35C-C)") (class "Default")
      (node (ref "R73") (pin "1") (pinfunction "1_1") (pintype "passive"))
      (node (ref "U35") (pin "12") (pinfunction "C_12") (pintype "passive"))
      (node (ref "U43") (pin "1") (pinfunction "G_1") (pintype "passive"))
    )
    (net (code "34") (name "Net-(U35D-A)") (class "Default")
      (node (ref "R68") (pin "2") (pinfunction "2_2") (pintype "passive"))
      (node (ref "U35") (pin "7") (pinfunction "A_7") (pintype "passive"))
    )
    (net (code "35") (name "Net-(U35D-C)") (class "Default")
      (node (ref "R74") (pin "1") (pinfunction "1_1") (pintype "passive"))
      (node (ref "U35") (pin "10") (pinfunction "C_10") (pintype "passive"))
      (node (ref "U44") (pin "1") (pinfunction "G_1") (pintype "passive"))
    )
    (net (code "36") (name "Net-(U42A-A)") (class "Default")
      (node (ref "R69") (pin "2") (pinfunction "2_2") (pintype "passive"))
      (node (ref "U42") (pin "1") (pinfunction "A_1") (pintype "passive"))
    )
    (net (code "37") (name "Net-(U42A-C)") (class "Default")
      (node (ref "R75") (pin "1") (pinfunction "1_1") (pintype "passive"))
      (node (ref "U42") (pin "16") (pinfunction "C_16") (pintype "passive"))
      (node (ref "U45") (pin "1") (pinfunction "G_1") (pintype "passive"))
    )
    (net (code "38") (name "Net-(U42B-A)") (class "Default")
      (node (ref "R70") (pin "2") (pinfunction "2_2") (pintype "passive"))
      (node (ref "U42") (pin "3") (pinfunction "A_3") (pintype "passive"))
    )
    (net (code "39") (name "Net-(U42B-C)") (class "Default")
      (node (ref "R76") (pin "1") (pinfunction "1_1") (pintype "passive"))
      (node (ref "U42") (pin "14") (pinfunction "C_14") (pintype "passive"))
      (node (ref "U46") (pin "1") (pinfunction "G_1") (pintype "passive"))
    )
    (net (code "40") (name "Net-(U42C-A)") (class "Default")
      (node (ref "R71") (pin "2") (pinfunction "2_2") (pintype "passive"))
      (node (ref "U42") (pin "5") (pinfunction "A_5") (pintype "passive"))
    )
    (net (code "41") (name "Net-(U42C-C)") (class "Default")
      (node (ref "R77") (pin "1") (pinfunction "1_1") (pintype "passive"))
      (node (ref "U42") (pin "12") (pinfunction "C_12") (pintype "passive"))
      (node (ref "U47") (pin "1") (pinfunction "G_1") (pintype "passive"))
    )
    (net (code "42") (name "Net-(U42D-A)") (class "Default")
      (node (ref "R72") (pin "2") (pinfunction "2_2") (pintype "passive"))
      (node (ref "U42") (pin "7") (pinfunction "A_7") (pintype "passive"))
    )
    (net (code "43") (name "Net-(U42D-C)") (class "Default")
      (node (ref "R78") (pin "1") (pinfunction "1_1") (pintype "passive"))
      (node (ref "U42") (pin "10") (pinfunction "C_10") (pintype "passive"))
      (node (ref "U48") (pin "1") (pinfunction "G_1") (pintype "passive"))
    )
    (net (code "44") (name "Net-(U49A-A)") (class "Default")
      (node (ref "R79") (pin "2") (pinfunction "2_2") (pintype "passive"))
      (node (ref "U49") (pin "1") (pinfunction "A_1") (pintype "passive"))
    )
    (net (code "45") (name "Net-(U49A-C)") (class "Default")
      (node (ref "R83") (pin "1") (pinfunction "1_1") (pintype "passive"))
      (node (ref "U49") (pin "16") (pinfunction "C_16") (pintype "passive"))
      (node (ref "U50") (pin "1") (pinfunction "G_1") (pintype "passive"))
    )
    (net (code "46") (name "Net-(U49B-A)") (class "Default")
      (node (ref "R80") (pin "2") (pinfunction "2_2") (pintype "passive"))
      (node (ref "U49") (pin "3") (pinfunction "A_3") (pintype "passive"))
    )
    (net (code "47") (name "Net-(U49B-C)") (class "Default")
      (node (ref "R84") (pin "1") (pinfunction "1_1") (pintype "passive"))
      (node (ref "U49") (pin "14") (pinfunction "C_14") (pintype "passive"))
      (node (ref "U51") (pin "1") (pinfunction "G_1") (pintype "passive"))
    )
    (net (code "48") (name "Net-(U49C-A)") (class "Default")
      (node (ref "R81") (pin "2") (pinfunction "2_2") (pintype "passive"))
      (node (ref "U49") (pin "5") (pinfunction "A_5") (pintype "passive"))
    )
    (net (code "49") (name "Net-(U49C-C)") (class "Default")
      (node (ref "R85") (pin "1") (pinfunction "1_1") (pintype "passive"))
      (node (ref "U49") (pin "12") (pinfunction "C_12") (pintype "passive"))
      (node (ref "U52") (pin "1") (pinfunction "G_1") (pintype "passive"))
    )
    (net (code "50") (name "Net-(U49D-A)") (class "Default")
      (node (ref "R82") (pin "2") (pinfunction "2_2") (pintype "passive"))
      (node (ref "U49") (pin "7") (pinfunction "A_7") (pintype "passive"))
    )
    (net (code "51") (name "Net-(U49D-C)") (class "Default")
      (node (ref "R86") (pin "1") (pinfunction "1_1") (pintype "passive"))
      (node (ref "U49") (pin "10") (pinfunction "C_10") (pintype "passive"))
      (node (ref "U53") (pin "1") (pinfunction "G_1") (pintype "passive"))
    )
    (net (code "52") (name "in_lock17") (class "Default")
      (node (ref "R55") (pin "1") (pinfunction "1_1") (pintype "passive"))
    )
    (net (code "53") (name "in_lock18") (class "Default")
      (node (ref "R56") (pin "1") (pinfunction "1_1") (pintype "passive"))
    )
    (net (code "54") (name "in_lock19") (class "Default")
      (node (ref "R57") (pin "1") (pinfunction "1_1") (pintype "passive"))
    )
    (net (code "55") (name "in_lock20") (class "Default")
      (node (ref "R58") (pin "1") (pinfunction "1_1") (pintype "passive"))
    )
    (net (code "56") (name "in_lock21") (class "Default")
      (node (ref "R59") (pin "1") (pinfunction "1_1") (pintype "passive"))
    )
    (net (code "57") (name "in_lock22") (class "Default")
      (node (ref "R60") (pin "1") (pinfunction "1_1") (pintype "passive"))
    )
    (net (code "58") (name "in_lock23") (class "Default")
      (node (ref "R67") (pin "1") (pinfunction "1_1") (pintype "passive"))
    )
    (net (code "59") (name "in_lock24") (class "Default")
      (node (ref "R68") (pin "1") (pinfunction "1_1") (pintype "passive"))
    )
    (net (code "60") (name "in_lock25") (class "Default")
      (node (ref "R69") (pin "1") (pinfunction "1_1") (pintype "passive"))
    )
    (net (code "61") (name "in_lock26") (class "Default")
      (node (ref "R70") (pin "1") (pinfunction "1_1") (pintype "passive"))
    )
    (net (code "62") (name "in_lock27") (class "Default")
      (node (ref "R71") (pin "1") (pinfunction "1_1") (pintype "passive"))
    )
    (net (code "63") (name "in_lock28") (class "Default")
      (node (ref "R72") (pin "1") (pinfunction "1_1") (pintype "passive"))
    )
    (net (code "64") (name "in_lock29") (class "Default")
      (node (ref "R79") (pin "1") (pinfunction "1_1") (pintype "passive"))
    )
    (net (code "65") (name "in_lock30") (class "Default")
      (node (ref "R80") (pin "1") (pinfunction "1_1") (pintype "passive"))
    )
    (net (code "66") (name "in_lock31") (class "Default")
      (node (ref "R81") (pin "1") (pinfunction "1_1") (pintype "passive"))
    )
    (net (code "67") (name "in_lock32") (class "Default")
      (node (ref "R82") (pin "1") (pinfunction "1_1") (pintype "passive"))
    )
  )
)
